# 03_-_CONNECTORS.net
KiCad netlist of a schematic drawn in Altium Designer
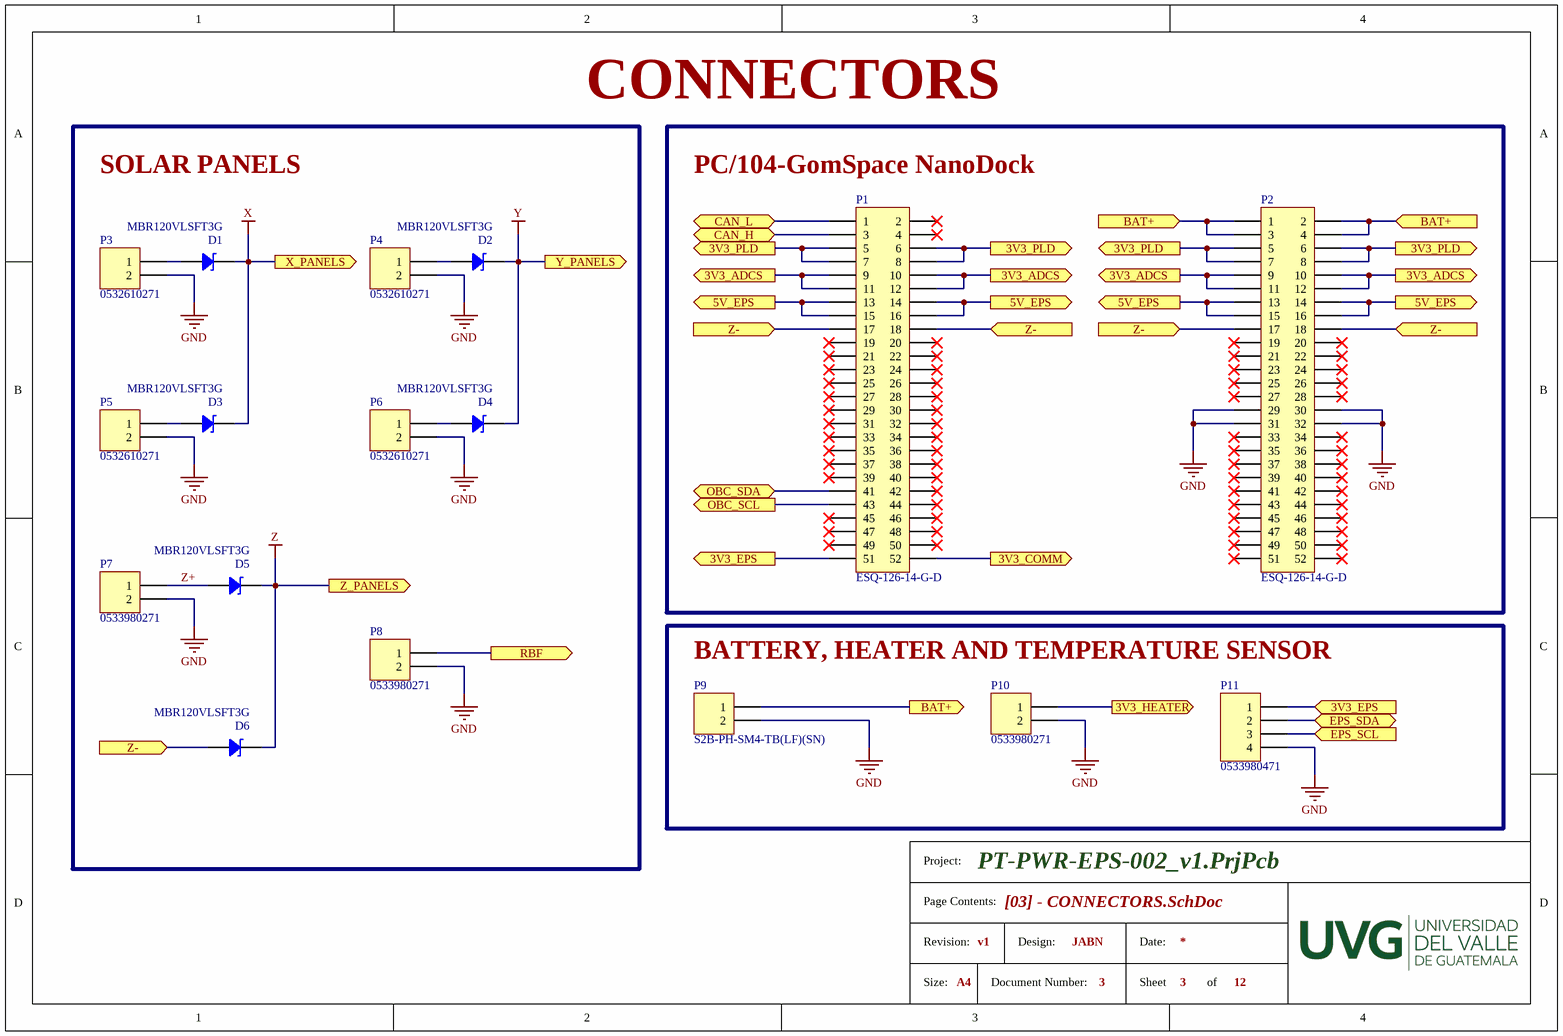
[diagram p0: [03] - CONNECTORS.SchDoc]

(export (version "E")
  (design (tool "Eeschema 10.0.6"))
  (components
    (comp (ref "D1")
      (value "MBR120VLSFT3G")
      (footprint "SOD123F")
      (description "DIODE SCHOTTKY 20V 1A SOD123FL")
      (fields (field (name "MANUFACTURER") "ON Semiconductor"))
      (libsource (lib "UVG") (part "MBR120VLSFT3G"))
    )
    (comp (ref "D2")
      (value "MBR120VLSFT3G")
      (footprint "SOD123F")
      (description "DIODE SCHOTTKY 20V 1A SOD123FL")
      (fields (field (name "MANUFACTURER") "ON Semiconductor"))
      (libsource (lib "UVG") (part "MBR120VLSFT3G"))
    )
    (comp (ref "D3")
      (value "MBR120VLSFT3G")
      (footprint "SOD123F")
      (description "DIODE SCHOTTKY 20V 1A SOD123FL")
      (fields (field (name "MANUFACTURER") "ON Semiconductor"))
      (libsource (lib "UVG") (part "MBR120VLSFT3G"))
    )
    (comp (ref "D4")
      (value "MBR120VLSFT3G")
      (footprint "SOD123F")
      (description "DIODE SCHOTTKY 20V 1A SOD123FL")
      (fields (field (name "MANUFACTURER") "ON Semiconductor"))
      (libsource (lib "UVG") (part "MBR120VLSFT3G"))
    )
    (comp (ref "D5")
      (value "MBR120VLSFT3G")
      (footprint "SOD123F")
      (description "DIODE SCHOTTKY 20V 1A SOD123FL")
      (fields (field (name "MANUFACTURER") "ON Semiconductor"))
      (libsource (lib "UVG") (part "MBR120VLSFT3G"))
    )
    (comp (ref "D6")
      (value "MBR120VLSFT3G")
      (footprint "SOD123F")
      (description "DIODE SCHOTTKY 20V 1A SOD123FL")
      (fields (field (name "MANUFACTURER") "ON Semiconductor"))
      (libsource (lib "UVG") (part "MBR120VLSFT3G"))
    )
    (comp (ref "P1")
      (value "ESQ-126-14-G-D")
      (footprint "ESQ-126-14-G-D")
      (description "CONN SOCKET 52POS 0.1 GOLD PCB")
      (fields (field (name "MANUFACTURER") "Samtec"))
      (libsource (lib "UVG") (part "ESQ-126-14-G-D"))
    )
    (comp (ref "P2")
      (value "ESQ-126-14-G-D")
      (footprint "ESQ-126-14-G-D")
      (description "CONN SOCKET 52POS 0.1 GOLD PCB")
      (fields (field (name "MANUFACTURER") "Samtec"))
      (libsource (lib "UVG") (part "ESQ-126-14-G-D"))
    )
    (comp (ref "P3")
      (value "0532610271")
      (footprint "0532610271")
      (description "CONN HEADER 2POS 1.25MM R/A SMD")
      (fields (field (name "MANUFACTURER") "Molex") (field (name "MANUFACTURER PART NUMBER") "53261-0271"))
      (libsource (lib "UVG") (part "0532610271"))
    )
    (comp (ref "P4")
      (value "0532610271")
      (footprint "0532610271")
      (description "CONN HEADER 2POS 1.25MM R/A SMD")
      (fields (field (name "MANUFACTURER") "Molex") (field (name "MANUFACTURER PART NUMBER") "53261-0271"))
      (libsource (lib "UVG") (part "0532610271"))
    )
    (comp (ref "P5")
      (value "0532610271")
      (footprint "0532610271")
      (description "CONN HEADER 2POS 1.25MM R/A SMD")
      (fields (field (name "MANUFACTURER") "Molex") (field (name "MANUFACTURER PART NUMBER") "53261-0271"))
      (libsource (lib "UVG") (part "0532610271"))
    )
    (comp (ref "P6")
      (value "0532610271")
      (footprint "0532610271")
      (description "CONN HEADER 2POS 1.25MM R/A SMD")
      (fields (field (name "MANUFACTURER") "Molex") (field (name "MANUFACTURER PART NUMBER") "53261-0271"))
      (libsource (lib "UVG") (part "0532610271"))
    )
    (comp (ref "P7")
      (value "0533980271")
      (footprint "0533980271")
      (description "CONN HEADER 2POS 1.25MM VERT SMD")
      (fields (field (name "MANUFACTURER") "Molex"))
      (libsource (lib "UVG") (part "0533980271"))
    )
    (comp (ref "P8")
      (value "0533980271")
      (footprint "0533980271")
      (description "CONN HEADER 2POS 1.25MM VERT SMD")
      (fields (field (name "MANUFACTURER") "Molex"))
      (libsource (lib "UVG") (part "0533980271"))
    )
    (comp (ref "P9")
      (value "S2B-PH-SM4-TB(LF)(SN)")
      (footprint "S2B-PH-SM4-TB(LF)(SN)")
      (description "CONN HEADER PH SIDE 2POS 2MM SMD")
      (fields (field (name "MANUFACTURER") "JST"))
      (libsource (lib "UVG") (part "S2B-PH-SM4-TB(LF)(SN)"))
    )
    (comp (ref "P10")
      (value "0533980271")
      (footprint "0533980271")
      (description "CONN HEADER 2POS 1.25MM VERT SMD")
      (fields (field (name "MANUFACTURER") "Molex"))
      (libsource (lib "UVG") (part "0533980271"))
    )
    (comp (ref "P11")
      (value "0533980471")
      (footprint "0533980471")
      (description "CONN HEADER 4POS 1.25MM VERT SMD")
      (fields (field (name "MANUFACTURER") "Molex") (field (name "MANUFACTURER PART NUMBER") "53398-0471"))
      (libsource (lib "UVG") (part "0533980471"))
    )
  )
  (nets
    (net (code "1") (name "/3V3_ADCS") (class "Default")
      (node (ref "P1") (pin "10") (pinfunction "10_10") (pintype "passive"))
      (node (ref "P1") (pin "11") (pinfunction "11_11") (pintype "passive"))
      (node (ref "P1") (pin "12") (pinfunction "12_12") (pintype "passive"))
      (node (ref "P1") (pin "9") (pinfunction "9_9") (pintype "passive"))
      (node (ref "P2") (pin "10") (pinfunction "10_10") (pintype "passive"))
      (node (ref "P2") (pin "11") (pinfunction "11_11") (pintype "passive"))
      (node (ref "P2") (pin "12") (pinfunction "12_12") (pintype "passive"))
      (node (ref "P2") (pin "9") (pinfunction "9_9") (pintype "passive"))
    )
    (net (code "2") (name "/3V3_COMM") (class "Default")
      (node (ref "P1") (pin "52") (pinfunction "52_52") (pintype "passive"))
    )
    (net (code "3") (name "/3V3_EPS") (class "Default")
      (node (ref "P1") (pin "51") (pinfunction "51_51") (pintype "passive"))
      (node (ref "P11") (pin "1") (pinfunction "1_1") (pintype "passive"))
    )
    (net (code "4") (name "/3V3_HEATER") (class "Default")
      (node (ref "P10") (pin "1") (pinfunction "1_1") (pintype "passive"))
    )
    (net (code "5") (name "/3V3_PLD") (class "Default")
      (node (ref "P1") (pin "5") (pinfunction "5_5") (pintype "passive"))
      (node (ref "P1") (pin "6") (pinfunction "6_6") (pintype "passive"))
      (node (ref "P1") (pin "7") (pinfunction "7_7") (pintype "passive"))
      (node (ref "P1") (pin "8") (pinfunction "8_8") (pintype "passive"))
      (node (ref "P2") (pin "5") (pinfunction "5_5") (pintype "passive"))
      (node (ref "P2") (pin "6") (pinfunction "6_6") (pintype "passive"))
      (node (ref "P2") (pin "7") (pinfunction "7_7") (pintype "passive"))
      (node (ref "P2") (pin "8") (pinfunction "8_8") (pintype "passive"))
    )
    (net (code "6") (name "/5V_EPS") (class "Default")
      (node (ref "P1") (pin "13") (pinfunction "13_13") (pintype "passive"))
      (node (ref "P1") (pin "14") (pinfunction "14_14") (pintype "passive"))
      (node (ref "P1") (pin "15") (pinfunction "15_15") (pintype "passive"))
      (node (ref "P1") (pin "16") (pinfunction "16_16") (pintype "passive"))
      (node (ref "P2") (pin "13") (pinfunction "13_13") (pintype "passive"))
      (node (ref "P2") (pin "14") (pinfunction "14_14") (pintype "passive"))
      (node (ref "P2") (pin "15") (pinfunction "15_15") (pintype "passive"))
      (node (ref "P2") (pin "16") (pinfunction "16_16") (pintype "passive"))
    )
    (net (code "7") (name "/BAT+") (class "Default")
      (node (ref "P2") (pin "1") (pinfunction "1_1") (pintype "passive"))
      (node (ref "P2") (pin "2") (pinfunction "2_2") (pintype "passive"))
      (node (ref "P2") (pin "3") (pinfunction "3_3") (pintype "passive"))
      (node (ref "P2") (pin "4") (pinfunction "4_4") (pintype "passive"))
      (node (ref "P9") (pin "1") (pinfunction "1_1") (pintype "passive"))
    )
    (net (code "8") (name "/CAN_H") (class "Default")
      (node (ref "P1") (pin "3") (pinfunction "3_3") (pintype "passive"))
    )
    (net (code "9") (name "/CAN_L") (class "Default")
      (node (ref "P1") (pin "1") (pinfunction "1_1") (pintype "passive"))
    )
    (net (code "10") (name "/EPS_SCL") (class "Default")
      (node (ref "P11") (pin "3") (pinfunction "3_3") (pintype "passive"))
    )
    (net (code "11") (name "/EPS_SDA") (class "Default")
      (node (ref "P11") (pin "2") (pinfunction "2_2") (pintype "passive"))
    )
    (net (code "12") (name "/OBC_SCL") (class "Default")
      (node (ref "P1") (pin "43") (pinfunction "43_43") (pintype "passive"))
    )
    (net (code "13") (name "/OBC_SDA") (class "Default")
      (node (ref "P1") (pin "41") (pinfunction "41_41") (pintype "passive"))
    )
    (net (code "14") (name "/RBF") (class "Default")
      (node (ref "P8") (pin "1") (pinfunction "1_1") (pintype "passive"))
    )
    (net (code "15") (name "/Z+") (class "Default")
      (node (ref "D5") (pin "1") (pinfunction "1_1") (pintype "passive"))
      (node (ref "P7") (pin "1") (pinfunction "1_1") (pintype "passive"))
    )
    (net (code "16") (name "/Z-") (class "Default")
      (node (ref "D6") (pin "1") (pinfunction "1_1") (pintype "passive"))
      (node (ref "P1") (pin "17") (pinfunction "17_17") (pintype "passive"))
      (node (ref "P1") (pin "18") (pinfunction "18_18") (pintype "passive"))
      (node (ref "P2") (pin "17") (pinfunction "17_17") (pintype "passive"))
      (node (ref "P2") (pin "18") (pinfunction "18_18") (pintype "passive"))
    )
    (net (code "17") (name "GND") (class "Default")
      (node (ref "P10") (pin "2") (pinfunction "2_2") (pintype "passive"))
      (node (ref "P11") (pin "4") (pinfunction "4_4") (pintype "passive"))
      (node (ref "P2") (pin "29") (pinfunction "29_29") (pintype "passive"))
      (node (ref "P2") (pin "30") (pinfunction "30_30") (pintype "passive"))
      (node (ref "P2") (pin "31") (pinfunction "31_31") (pintype "passive"))
      (node (ref "P2") (pin "32") (pinfunction "32_32") (pintype "passive"))
      (node (ref "P3") (pin "2") (pinfunction "2_2") (pintype "passive"))
      (node (ref "P4") (pin "2") (pinfunction "2_2") (pintype "passive"))
      (node (ref "P5") (pin "2") (pinfunction "2_2") (pintype "passive"))
      (node (ref "P6") (pin "2") (pinfunction "2_2") (pintype "passive"))
      (node (ref "P7") (pin "2") (pinfunction "2_2") (pintype "passive"))
      (node (ref "P8") (pin "2") (pinfunction "2_2") (pintype "passive"))
      (node (ref "P9") (pin "2") (pinfunction "2_2") (pintype "passive"))
    )
    (net (code "18") (name "Net-(D1-Pad1)") (class "Default")
      (node (ref "D1") (pin "1") (pinfunction "1_1") (pintype "passive"))
      (node (ref "P3") (pin "1") (pinfunction "1_1") (pintype "passive"))
    )
    (net (code "19") (name "Net-(D2-Pad1)") (class "Default")
      (node (ref "D2") (pin "1") (pinfunction "1_1") (pintype "passive"))
      (node (ref "P4") (pin "1") (pinfunction "1_1") (pintype "passive"))
    )
    (net (code "20") (name "Net-(D3-Pad1)") (class "Default")
      (node (ref "D3") (pin "1") (pinfunction "1_1") (pintype "passive"))
      (node (ref "P5") (pin "1") (pinfunction "1_1") (pintype "passive"))
    )
    (net (code "21") (name "Net-(D4-Pad1)") (class "Default")
      (node (ref "D4") (pin "1") (pinfunction "1_1") (pintype "passive"))
      (node (ref "P6") (pin "1") (pinfunction "1_1") (pintype "passive"))
    )
    (net (code "22") (name "X") (class "Default")
      (node (ref "D1") (pin "2") (pinfunction "2_2") (pintype "passive"))
      (node (ref "D3") (pin "2") (pinfunction "2_2") (pintype "passive"))
    )
    (net (code "23") (name "Y") (class "Default")
      (node (ref "D2") (pin "2") (pinfunction "2_2") (pintype "passive"))
      (node (ref "D4") (pin "2") (pinfunction "2_2") (pintype "passive"))
    )
    (net (code "24") (name "Z") (class "Default")
      (node (ref "D5") (pin "2") (pinfunction "2_2") (pintype "passive"))
      (node (ref "D6") (pin "2") (pinfunction "2_2") (pintype "passive"))
    )
    (net (code "25") (name "unconnected-(P1-Pad2)") (class "Default")
      (node (ref "P1") (pin "2") (pinfunction "2_2") (pintype "passive+no_connect"))
    )
    (net (code "26") (name "unconnected-(P1-Pad4)") (class "Default")
      (node (ref "P1") (pin "4") (pinfunction "4_4") (pintype "passive+no_connect"))
    )
    (net (code "27") (name "unconnected-(P1-Pad19)") (class "Default")
      (node (ref "P1") (pin "19") (pinfunction "19_19") (pintype "passive+no_connect"))
    )
    (net (code "28") (name "unconnected-(P1-Pad20)") (class "Default")
      (node (ref "P1") (pin "20") (pinfunction "20_20") (pintype "passive+no_connect"))
    )
    (net (code "29") (name "unconnected-(P1-Pad21)") (class "Default")
      (node (ref "P1") (pin "21") (pinfunction "21_21") (pintype "passive+no_connect"))
    )
    (net (code "30") (name "unconnected-(P1-Pad22)") (class "Default")
      (node (ref "P1") (pin "22") (pinfunction "22_22") (pintype "passive+no_connect"))
    )
    (net (code "31") (name "unconnected-(P1-Pad23)") (class "Default")
      (node (ref "P1") (pin "23") (pinfunction "23_23") (pintype "passive+no_connect"))
    )
    (net (code "32") (name "unconnected-(P1-Pad24)") (class "Default")
      (node (ref "P1") (pin "24") (pinfunction "24_24") (pintype "passive+no_connect"))
    )
    (net (code "33") (name "unconnected-(P1-Pad25)") (class "Default")
      (node (ref "P1") (pin "25") (pinfunction "25_25") (pintype "passive+no_connect"))
    )
    (net (code "34") (name "unconnected-(P1-Pad26)") (class "Default")
      (node (ref "P1") (pin "26") (pinfunction "26_26") (pintype "passive+no_connect"))
    )
    (net (code "35") (name "unconnected-(P1-Pad27)") (class "Default")
      (node (ref "P1") (pin "27") (pinfunction "27_27") (pintype "passive+no_connect"))
    )
    (net (code "36") (name "unconnected-(P1-Pad28)") (class "Default")
      (node (ref "P1") (pin "28") (pinfunction "28_28") (pintype "passive+no_connect"))
    )
    (net (code "37") (name "unconnected-(P1-Pad29)") (class "Default")
      (node (ref "P1") (pin "29") (pinfunction "29_29") (pintype "passive+no_connect"))
    )
    (net (code "38") (name "unconnected-(P1-Pad30)") (class "Default")
      (node (ref "P1") (pin "30") (pinfunction "30_30") (pintype "passive+no_connect"))
    )
    (net (code "39") (name "unconnected-(P1-Pad31)") (class "Default")
      (node (ref "P1") (pin "31") (pinfunction "31_31") (pintype "passive+no_connect"))
    )
    (net (code "40") (name "unconnected-(P1-Pad32)") (class "Default")
      (node (ref "P1") (pin "32") (pinfunction "32_32") (pintype "passive+no_connect"))
    )
    (net (code "41") (name "unconnected-(P1-Pad33)") (class "Default")
      (node (ref "P1") (pin "33") (pinfunction "33_33") (pintype "passive+no_connect"))
    )
    (net (code "42") (name "unconnected-(P1-Pad34)") (class "Default")
      (node (ref "P1") (pin "34") (pinfunction "34_34") (pintype "passive+no_connect"))
    )
    (net (code "43") (name "unconnected-(P1-Pad35)") (class "Default")
      (node (ref "P1") (pin "35") (pinfunction "35_35") (pintype "passive+no_connect"))
    )
    (net (code "44") (name "unconnected-(P1-Pad36)") (class "Default")
      (node (ref "P1") (pin "36") (pinfunction "36_36") (pintype "passive+no_connect"))
    )
    (net (code "45") (name "unconnected-(P1-Pad37)") (class "Default")
      (node (ref "P1") (pin "37") (pinfunction "37_37") (pintype "passive+no_connect"))
    )
    (net (code "46") (name "unconnected-(P1-Pad38)") (class "Default")
      (node (ref "P1") (pin "38") (pinfunction "38_38") (pintype "passive+no_connect"))
    )
    (net (code "47") (name "unconnected-(P1-Pad39)") (class "Default")
      (node (ref "P1") (pin "39") (pinfunction "39_39") (pintype "passive+no_connect"))
    )
    (net (code "48") (name "unconnected-(P1-Pad40)") (class "Default")
      (node (ref "P1") (pin "40") (pinfunction "40_40") (pintype "passive+no_connect"))
    )
    (net (code "49") (name "unconnected-(P1-Pad42)") (class "Default")
      (node (ref "P1") (pin "42") (pinfunction "42_42") (pintype "passive+no_connect"))
    )
    (net (code "50") (name "unconnected-(P1-Pad44)") (class "Default")
      (node (ref "P1") (pin "44") (pinfunction "44_44") (pintype "passive+no_connect"))
    )
    (net (code "51") (name "unconnected-(P1-Pad45)") (class "Default")
      (node (ref "P1") (pin "45") (pinfunction "45_45") (pintype "passive+no_connect"))
    )
    (net (code "52") (name "unconnected-(P1-Pad46)") (class "Default")
      (node (ref "P1") (pin "46") (pinfunction "46_46") (pintype "passive+no_connect"))
    )
    (net (code "53") (name "unconnected-(P1-Pad47)") (class "Default")
      (node (ref "P1") (pin "47") (pinfunction "47_47") (pintype "passive+no_connect"))
    )
    (net (code "54") (name "unconnected-(P1-Pad48)") (class "Default")
      (node (ref "P1") (pin "48") (pinfunction "48_48") (pintype "passive+no_connect"))
    )
    (net (code "55") (name "unconnected-(P1-Pad49)") (class "Default")
      (node (ref "P1") (pin "49") (pinfunction "49_49") (pintype "passive+no_connect"))
    )
    (net (code "56") (name "unconnected-(P1-Pad50)") (class "Default")
      (node (ref "P1") (pin "50") (pinfunction "50_50") (pintype "passive+no_connect"))
    )
    (net (code "57") (name "unconnected-(P2-Pad19)") (class "Default")
      (node (ref "P2") (pin "19") (pinfunction "19_19") (pintype "passive+no_connect"))
    )
    (net (code "58") (name "unconnected-(P2-Pad20)") (class "Default")
      (node (ref "P2") (pin "20") (pinfunction "20_20") (pintype "passive+no_connect"))
    )
    (net (code "59") (name "unconnected-(P2-Pad21)") (class "Default")
      (node (ref "P2") (pin "21") (pinfunction "21_21") (pintype "passive+no_connect"))
    )
    (net (code "60") (name "unconnected-(P2-Pad22)") (class "Default")
      (node (ref "P2") (pin "22") (pinfunction "22_22") (pintype "passive+no_connect"))
    )
    (net (code "61") (name "unconnected-(P2-Pad23)") (class "Default")
      (node (ref "P2") (pin "23") (pinfunction "23_23") (pintype "passive+no_connect"))
    )
    (net (code "62") (name "unconnected-(P2-Pad24)") (class "Default")
      (node (ref "P2") (pin "24") (pinfunction "24_24") (pintype "passive+no_connect"))
    )
    (net (code "63") (name "unconnected-(P2-Pad25)") (class "Default")
      (node (ref "P2") (pin "25") (pinfunction "25_25") (pintype "passive+no_connect"))
    )
    (net (code "64") (name "unconnected-(P2-Pad26)") (class "Default")
      (node (ref "P2") (pin "26") (pinfunction "26_26") (pintype "passive+no_connect"))
    )
    (net (code "65") (name "unconnected-(P2-Pad27)") (class "Default")
      (node (ref "P2") (pin "27") (pinfunction "27_27") (pintype "passive+no_connect"))
    )
    (net (code "66") (name "unconnected-(P2-Pad28)") (class "Default")
      (node (ref "P2") (pin "28") (pinfunction "28_28") (pintype "passive+no_connect"))
    )
    (net (code "67") (name "unconnected-(P2-Pad33)") (class "Default")
      (node (ref "P2") (pin "33") (pinfunction "33_33") (pintype "passive+no_connect"))
    )
    (net (code "68") (name "unconnected-(P2-Pad34)") (class "Default")
      (node (ref "P2") (pin "34") (pinfunction "34_34") (pintype "passive+no_connect"))
    )
    (net (code "69") (name "unconnected-(P2-Pad35)") (class "Default")
      (node (ref "P2") (pin "35") (pinfunction "35_35") (pintype "passive+no_connect"))
    )
    (net (code "70") (name "unconnected-(P2-Pad36)") (class "Default")
      (node (ref "P2") (pin "36") (pinfunction "36_36") (pintype "passive+no_connect"))
    )
    (net (code "71") (name "unconnected-(P2-Pad37)") (class "Default")
      (node (ref "P2") (pin "37") (pinfunction "37_37") (pintype "passive+no_connect"))
    )
    (net (code "72") (name "unconnected-(P2-Pad38)") (class "Default")
      (node (ref "P2") (pin "38") (pinfunction "38_38") (pintype "passive+no_connect"))
    )
    (net (code "73") (name "unconnected-(P2-Pad39)") (class "Default")
      (node (ref "P2") (pin "39") (pinfunction "39_39") (pintype "passive+no_connect"))
    )
    (net (code "74") (name "unconnected-(P2-Pad40)") (class "Default")
      (node (ref "P2") (pin "40") (pinfunction "40_40") (pintype "passive+no_connect"))
    )
    (net (code "75") (name "unconnected-(P2-Pad41)") (class "Default")
      (node (ref "P2") (pin "41") (pinfunction "41_41") (pintype "passive+no_connect"))
    )
    (net (code "76") (name "unconnected-(P2-Pad42)") (class "Default")
      (node (ref "P2") (pin "42") (pinfunction "42_42") (pintype "passive+no_connect"))
    )
    (net (code "77") (name "unconnected-(P2-Pad43)") (class "Default")
      (node (ref "P2") (pin "43") (pinfunction "43_43") (pintype "passive+no_connect"))
    )
    (net (code "78") (name "unconnected-(P2-Pad44)") (class "Default")
      (node (ref "P2") (pin "44") (pinfunction "44_44") (pintype "passive+no_connect"))
    )
    (net (code "79") (name "unconnected-(P2-Pad45)") (class "Default")
      (node (ref "P2") (pin "45") (pinfunction "45_45") (pintype "passive+no_connect"))
    )
    (net (code "80") (name "unconnected-(P2-Pad46)") (class "Default")
      (node (ref "P2") (pin "46") (pinfunction "46_46") (pintype "passive+no_connect"))
    )
    (net (code "81") (name "unconnected-(P2-Pad47)") (class "Default")
      (node (ref "P2") (pin "47") (pinfunction "47_47") (pintype "passive+no_connect"))
    )
    (net (code "82") (name "unconnected-(P2-Pad48)") (class "Default")
      (node (ref "P2") (pin "48") (pinfunction "48_48") (pintype "passive+no_connect"))
    )
    (net (code "83") (name "unconnected-(P2-Pad49)") (class "Default")
      (node (ref "P2") (pin "49") (pinfunction "49_49") (pintype "passive+no_connect"))
    )
    (net (code "84") (name "unconnected-(P2-Pad50)") (class "Default")
      (node (ref "P2") (pin "50") (pinfunction "50_50") (pintype "passive+no_connect"))
    )
    (net (code "85") (name "unconnected-(P2-Pad51)") (class "Default")
      (node (ref "P2") (pin "51") (pinfunction "51_51") (pintype "passive+no_connect"))
    )
    (net (code "86") (name "unconnected-(P2-Pad52)") (class "Default")
      (node (ref "P2") (pin "52") (pinfunction "52_52") (pintype "passive+no_connect"))
    )
  )
)
